# ForceSensingBase_Schematics.net
KiCad netlist of a schematic drawn in EasyEDA
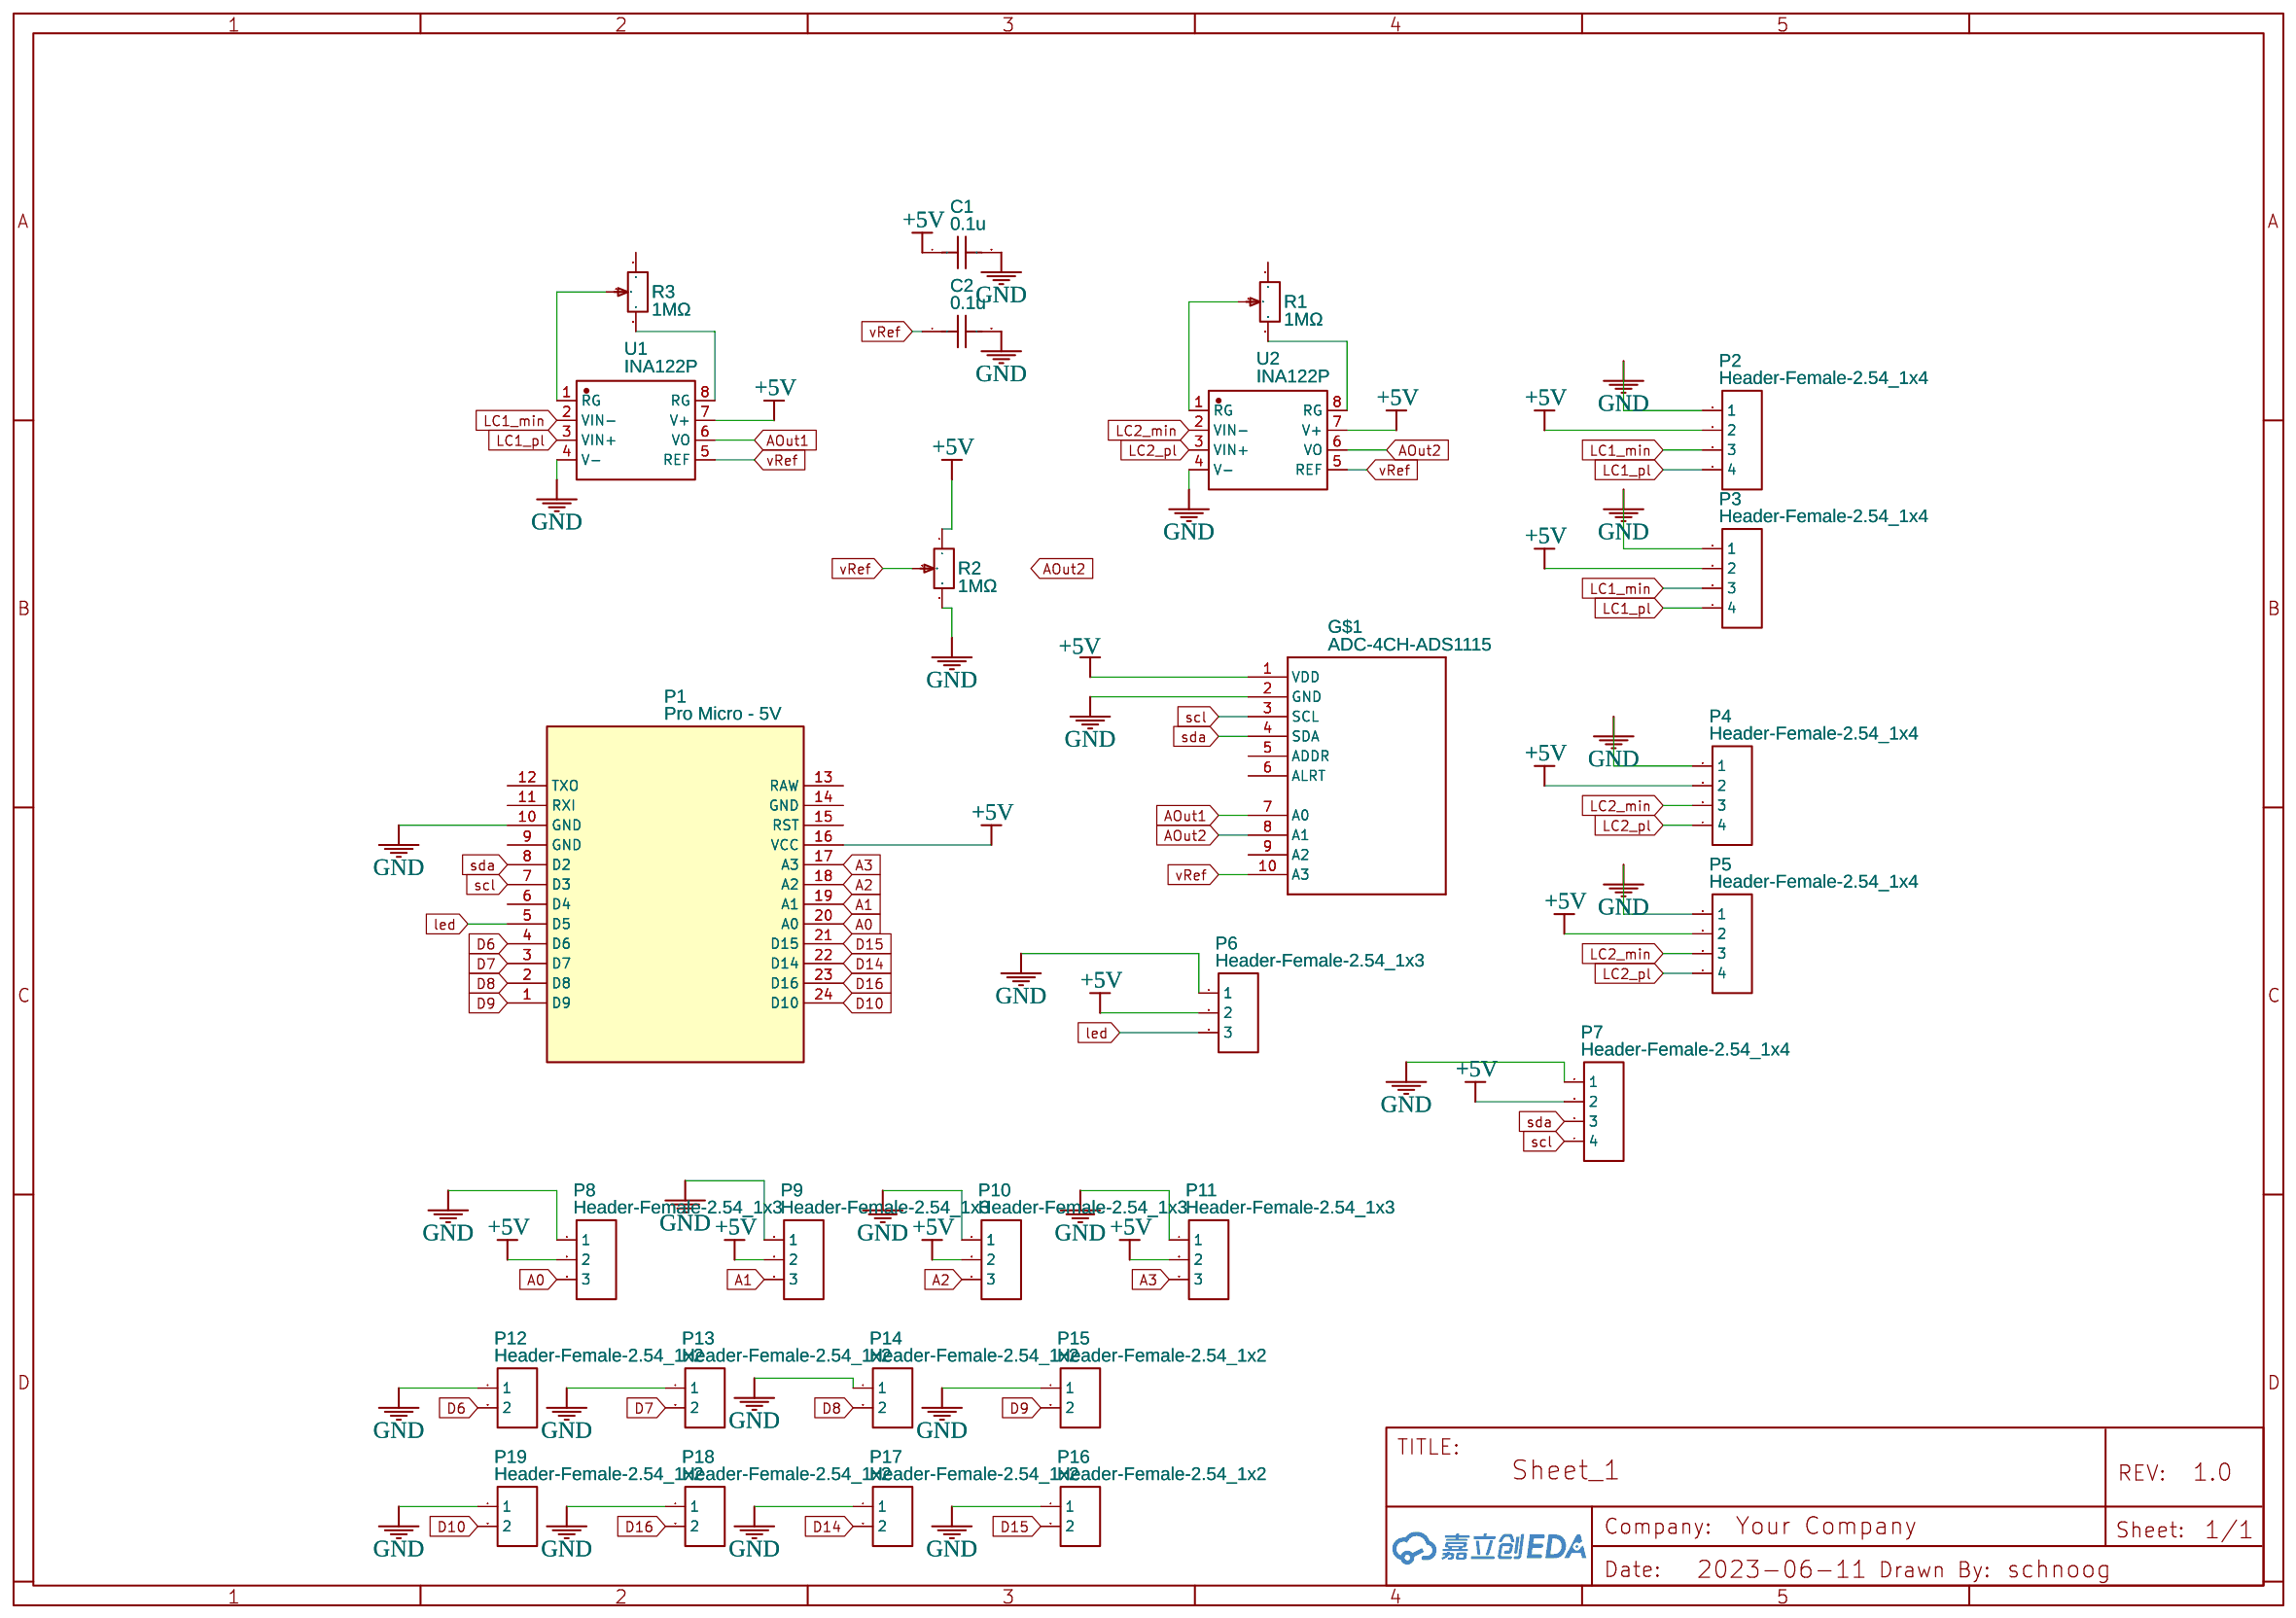
[diagram p0: schematic sheet]

(export (version "E")
  (design (tool "Eeschema 10.0.6"))
  (components
    (comp (ref "C1") (value "0.1u") (libsource (lib "") (part "C_1206_US")))
    (comp (ref "C2") (value "0.1u") (libsource (lib "") (part "C_1206_US")))
    (comp (ref "G$1") (value "ADC-4CH-ADS1115") (libsource (lib "") (part "ADC-4CH-ADS1115")))
    (comp (ref "P1") (value "Pro Micro - 5V") (libsource (lib "") (part "Pro Micro - 5V")))
    (comp (ref "P2")
      (value "Header-Female-2.54_1x4")
      (fields (field (name "BOM_Supplier Part") "C124413"))
      (libsource (lib "") (part "Header-Female-2.54_1x4"))
    )
    (comp (ref "P3")
      (value "Header-Female-2.54_1x4")
      (fields (field (name "BOM_Supplier Part") "C124413"))
      (libsource (lib "") (part "Header-Female-2.54_1x4"))
    )
    (comp (ref "P4")
      (value "Header-Female-2.54_1x4")
      (fields (field (name "BOM_Supplier Part") "C124413"))
      (libsource (lib "") (part "Header-Female-2.54_1x4"))
    )
    (comp (ref "P5")
      (value "Header-Female-2.54_1x4")
      (fields (field (name "BOM_Supplier Part") "C124413"))
      (libsource (lib "") (part "Header-Female-2.54_1x4"))
    )
    (comp (ref "P6")
      (value "Header-Female-2.54_1x3")
      (fields
        (field (name "BOM_Manufacturer Part") "2.54-1*3P母")
        (field (name "BOM_Supplier Part") "C146243")
      )
      (libsource (lib "") (part "Header-Female-2.54_1x3"))
    )
    (comp (ref "P7")
      (value "Header-Female-2.54_1x4")
      (fields (field (name "BOM_Supplier Part") "C124413"))
      (libsource (lib "") (part "Header-Female-2.54_1x4"))
    )
    (comp (ref "P8")
      (value "Header-Female-2.54_1x3")
      (fields
        (field (name "BOM_Manufacturer Part") "2.54-1*3P母")
        (field (name "BOM_Supplier Part") "C146243")
      )
      (libsource (lib "") (part "Header-Female-2.54_1x3"))
    )
    (comp (ref "P9")
      (value "Header-Female-2.54_1x3")
      (fields
        (field (name "BOM_Manufacturer Part") "2.54-1*3P母")
        (field (name "BOM_Supplier Part") "C146243")
      )
      (libsource (lib "") (part "Header-Female-2.54_1x3"))
    )
    (comp (ref "P10")
      (value "Header-Female-2.54_1x3")
      (fields
        (field (name "BOM_Manufacturer Part") "2.54-1*3P母")
        (field (name "BOM_Supplier Part") "C146243")
      )
      (libsource (lib "") (part "Header-Female-2.54_1x3"))
    )
    (comp (ref "P11")
      (value "Header-Female-2.54_1x3")
      (fields
        (field (name "BOM_Manufacturer Part") "2.54-1*3P母")
        (field (name "BOM_Supplier Part") "C146243")
      )
      (libsource (lib "") (part "Header-Female-2.54_1x3"))
    )
    (comp (ref "P12")
      (value "Header-Female-2.54_1x2")
      (fields (field (name "BOM_Manufacturer Part") "2.54-1*2P母") (field (name "BOM_Supplier Part") "C49661"))
      (libsource (lib "") (part "Header-Female-2.54_1x2"))
    )
    (comp (ref "P13")
      (value "Header-Female-2.54_1x2")
      (fields (field (name "BOM_Manufacturer Part") "2.54-1*2P母") (field (name "BOM_Supplier Part") "C49661"))
      (libsource (lib "") (part "Header-Female-2.54_1x2"))
    )
    (comp (ref "P14")
      (value "Header-Female-2.54_1x2")
      (fields (field (name "BOM_Manufacturer Part") "2.54-1*2P母") (field (name "BOM_Supplier Part") "C49661"))
      (libsource (lib "") (part "Header-Female-2.54_1x2"))
    )
    (comp (ref "P15")
      (value "Header-Female-2.54_1x2")
      (fields (field (name "BOM_Manufacturer Part") "2.54-1*2P母") (field (name "BOM_Supplier Part") "C49661"))
      (libsource (lib "") (part "Header-Female-2.54_1x2"))
    )
    (comp (ref "P16")
      (value "Header-Female-2.54_1x2")
      (fields (field (name "BOM_Manufacturer Part") "2.54-1*2P母") (field (name "BOM_Supplier Part") "C49661"))
      (libsource (lib "") (part "Header-Female-2.54_1x2"))
    )
    (comp (ref "P17")
      (value "Header-Female-2.54_1x2")
      (fields (field (name "BOM_Manufacturer Part") "2.54-1*2P母") (field (name "BOM_Supplier Part") "C49661"))
      (libsource (lib "") (part "Header-Female-2.54_1x2"))
    )
    (comp (ref "P18")
      (value "Header-Female-2.54_1x2")
      (fields (field (name "BOM_Manufacturer Part") "2.54-1*2P母") (field (name "BOM_Supplier Part") "C49661"))
      (libsource (lib "") (part "Header-Female-2.54_1x2"))
    )
    (comp (ref "P19")
      (value "Header-Female-2.54_1x2")
      (fields (field (name "BOM_Manufacturer Part") "2.54-1*2P母") (field (name "BOM_Supplier Part") "C49661"))
      (libsource (lib "") (part "Header-Female-2.54_1x2"))
    )
    (comp (ref "R1")
      (value "1MΩ")
      (fields
        (field (name "BOM_Manufacturer Part") "3296W-1-105LF")
        (field (name "BOM_Supplier Part") "C83687")
      )
      (libsource (lib "") (part "3296W-1-105LF"))
    )
    (comp (ref "R2")
      (value "1MΩ")
      (fields
        (field (name "BOM_Manufacturer Part") "3296W-1-105LF")
        (field (name "BOM_Supplier Part") "C83687")
      )
      (libsource (lib "") (part "3296W-1-105LF"))
    )
    (comp (ref "R3")
      (value "1MΩ")
      (fields
        (field (name "BOM_Manufacturer Part") "3296W-1-105LF")
        (field (name "BOM_Supplier Part") "C83687")
      )
      (libsource (lib "") (part "3296W-1-105LF"))
    )
    (comp (ref "U1")
      (value "INA122P")
      (fields (field (name "BOM_Supplier Part") "C1346816"))
      (libsource (lib "") (part "INA122P"))
    )
    (comp (ref "U2")
      (value "INA122P")
      (fields (field (name "BOM_Supplier Part") "C1346816"))
      (libsource (lib "") (part "INA122P"))
    )
  )
  (nets
    (net (code "1") (name "+5V") (class "Default")
      (node (ref "C1") (pin "1") (pinfunction "1_1") (pintype "unspecified"))
      (node (ref "G$1") (pin "1") (pinfunction "VDD_1") (pintype "bidirectional"))
      (node (ref "P1") (pin "16") (pinfunction "VCC_16") (pintype "unspecified"))
      (node (ref "P10") (pin "2") (pinfunction "2_2") (pintype "input"))
      (node (ref "P11") (pin "2") (pinfunction "2_2") (pintype "input"))
      (node (ref "P2") (pin "2") (pinfunction "2_2") (pintype "input"))
      (node (ref "P3") (pin "2") (pinfunction "2_2") (pintype "input"))
      (node (ref "P4") (pin "2") (pinfunction "2_2") (pintype "input"))
      (node (ref "P5") (pin "2") (pinfunction "2_2") (pintype "input"))
      (node (ref "P6") (pin "2") (pinfunction "2_2") (pintype "input"))
      (node (ref "P7") (pin "2") (pinfunction "2_2") (pintype "input"))
      (node (ref "P8") (pin "2") (pinfunction "2_2") (pintype "input"))
      (node (ref "P9") (pin "2") (pinfunction "2_2") (pintype "input"))
      (node (ref "R2") (pin "1") (pinfunction "1_1") (pintype "input"))
      (node (ref "U1") (pin "7") (pinfunction "V+_7") (pintype "unspecified"))
      (node (ref "U2") (pin "7") (pinfunction "V+_7") (pintype "unspecified"))
    )
    (net (code "2") (name "A0") (class "Default")
      (node (ref "P1") (pin "20") (pinfunction "A0_20") (pintype "unspecified"))
      (node (ref "P8") (pin "3") (pinfunction "3_3") (pintype "input"))
    )
    (net (code "3") (name "A1") (class "Default")
      (node (ref "P1") (pin "19") (pinfunction "A1_19") (pintype "unspecified"))
      (node (ref "P9") (pin "3") (pinfunction "3_3") (pintype "input"))
    )
    (net (code "4") (name "A2") (class "Default")
      (node (ref "P1") (pin "18") (pinfunction "A2_18") (pintype "unspecified"))
      (node (ref "P10") (pin "3") (pinfunction "3_3") (pintype "input"))
    )
    (net (code "5") (name "A3") (class "Default")
      (node (ref "P1") (pin "17") (pinfunction "A3_17") (pintype "unspecified"))
      (node (ref "P11") (pin "3") (pinfunction "3_3") (pintype "input"))
    )
    (net (code "6") (name "AOut1") (class "Default")
      (node (ref "G$1") (pin "7") (pinfunction "A0_7") (pintype "bidirectional"))
      (node (ref "U1") (pin "6") (pinfunction "VO_6") (pintype "unspecified"))
    )
    (net (code "7") (name "AOut2") (class "Default")
      (node (ref "G$1") (pin "8") (pinfunction "A1_8") (pintype "bidirectional"))
      (node (ref "U2") (pin "6") (pinfunction "VO_6") (pintype "unspecified"))
    )
    (net (code "8") (name "D6") (class "Default")
      (node (ref "P1") (pin "4") (pinfunction "D6_4") (pintype "unspecified"))
      (node (ref "P12") (pin "2") (pinfunction "2_2") (pintype "input"))
    )
    (net (code "9") (name "D7") (class "Default")
      (node (ref "P1") (pin "3") (pinfunction "D7_3") (pintype "unspecified"))
      (node (ref "P13") (pin "2") (pinfunction "2_2") (pintype "input"))
    )
    (net (code "10") (name "D8") (class "Default")
      (node (ref "P1") (pin "2") (pinfunction "D8_2") (pintype "unspecified"))
      (node (ref "P14") (pin "2") (pinfunction "2_2") (pintype "input"))
    )
    (net (code "11") (name "D9") (class "Default")
      (node (ref "P1") (pin "1") (pinfunction "D9_1") (pintype "unspecified"))
      (node (ref "P15") (pin "2") (pinfunction "2_2") (pintype "input"))
    )
    (net (code "12") (name "D10") (class "Default")
      (node (ref "P1") (pin "24") (pinfunction "D10_24") (pintype "unspecified"))
      (node (ref "P19") (pin "2") (pinfunction "2_2") (pintype "input"))
    )
    (net (code "13") (name "D14") (class "Default")
      (node (ref "P1") (pin "22") (pinfunction "D14_22") (pintype "unspecified"))
      (node (ref "P17") (pin "2") (pinfunction "2_2") (pintype "input"))
    )
    (net (code "14") (name "D15") (class "Default")
      (node (ref "P1") (pin "21") (pinfunction "D15_21") (pintype "unspecified"))
      (node (ref "P16") (pin "2") (pinfunction "2_2") (pintype "input"))
    )
    (net (code "15") (name "D16") (class "Default")
      (node (ref "P1") (pin "23") (pinfunction "D16_23") (pintype "unspecified"))
      (node (ref "P18") (pin "2") (pinfunction "2_2") (pintype "input"))
    )
    (net (code "16") (name "GND") (class "Default")
      (node (ref "C1") (pin "2") (pinfunction "2_2") (pintype "unspecified"))
      (node (ref "C2") (pin "2") (pinfunction "2_2") (pintype "unspecified"))
      (node (ref "G$1") (pin "2") (pinfunction "GND_2") (pintype "bidirectional"))
      (node (ref "P1") (pin "10") (pinfunction "GND_10") (pintype "unspecified"))
      (node (ref "P10") (pin "1") (pinfunction "1_1") (pintype "input"))
      (node (ref "P11") (pin "1") (pinfunction "1_1") (pintype "input"))
      (node (ref "P12") (pin "1") (pinfunction "1_1") (pintype "input"))
      (node (ref "P13") (pin "1") (pinfunction "1_1") (pintype "input"))
      (node (ref "P14") (pin "1") (pinfunction "1_1") (pintype "input"))
      (node (ref "P15") (pin "1") (pinfunction "1_1") (pintype "input"))
      (node (ref "P16") (pin "1") (pinfunction "1_1") (pintype "input"))
      (node (ref "P17") (pin "1") (pinfunction "1_1") (pintype "input"))
      (node (ref "P18") (pin "1") (pinfunction "1_1") (pintype "input"))
      (node (ref "P19") (pin "1") (pinfunction "1_1") (pintype "input"))
      (node (ref "P2") (pin "1") (pinfunction "1_1") (pintype "input"))
      (node (ref "P3") (pin "1") (pinfunction "1_1") (pintype "input"))
      (node (ref "P4") (pin "1") (pinfunction "1_1") (pintype "input"))
      (node (ref "P5") (pin "1") (pinfunction "1_1") (pintype "input"))
      (node (ref "P6") (pin "1") (pinfunction "1_1") (pintype "input"))
      (node (ref "P7") (pin "1") (pinfunction "1_1") (pintype "input"))
      (node (ref "P8") (pin "1") (pinfunction "1_1") (pintype "input"))
      (node (ref "P9") (pin "1") (pinfunction "1_1") (pintype "input"))
      (node (ref "R2") (pin "3") (pinfunction "3_3") (pintype "input"))
      (node (ref "U1") (pin "4") (pinfunction "V-_4") (pintype "unspecified"))
      (node (ref "U2") (pin "4") (pinfunction "V-_4") (pintype "unspecified"))
    )
    (net (code "17") (name "LC1_min") (class "Default")
      (node (ref "P2") (pin "3") (pinfunction "3_3") (pintype "input"))
      (node (ref "P3") (pin "3") (pinfunction "3_3") (pintype "input"))
      (node (ref "U1") (pin "2") (pinfunction "VIN-_2") (pintype "unspecified"))
    )
    (net (code "18") (name "LC1_pl") (class "Default")
      (node (ref "P2") (pin "4") (pinfunction "4_4") (pintype "input"))
      (node (ref "P3") (pin "4") (pinfunction "4_4") (pintype "input"))
      (node (ref "U1") (pin "3") (pinfunction "VIN+_3") (pintype "unspecified"))
    )
    (net (code "19") (name "LC2_min") (class "Default")
      (node (ref "P4") (pin "3") (pinfunction "3_3") (pintype "input"))
      (node (ref "P5") (pin "3") (pinfunction "3_3") (pintype "input"))
      (node (ref "U2") (pin "2") (pinfunction "VIN-_2") (pintype "unspecified"))
    )
    (net (code "20") (name "LC2_pl") (class "Default")
      (node (ref "P4") (pin "4") (pinfunction "4_4") (pintype "input"))
      (node (ref "P5") (pin "4") (pinfunction "4_4") (pintype "input"))
      (node (ref "U2") (pin "3") (pinfunction "VIN+_3") (pintype "unspecified"))
    )
    (net (code "21") (name "Net-(R1-Pad2)") (class "Default")
      (node (ref "R1") (pin "2") (pinfunction "2_2") (pintype "input"))
      (node (ref "U2") (pin "1") (pinfunction "RG_1") (pintype "unspecified"))
    )
    (net (code "22") (name "Net-(R1-Pad3)") (class "Default")
      (node (ref "R1") (pin "3") (pinfunction "3_3") (pintype "input"))
      (node (ref "U2") (pin "8") (pinfunction "RG_8") (pintype "unspecified"))
    )
    (net (code "23") (name "Net-(R3-Pad2)") (class "Default")
      (node (ref "R3") (pin "2") (pinfunction "2_2") (pintype "input"))
      (node (ref "U1") (pin "1") (pinfunction "RG_1") (pintype "unspecified"))
    )
    (net (code "24") (name "Net-(R3-Pad3)") (class "Default")
      (node (ref "R3") (pin "3") (pinfunction "3_3") (pintype "input"))
      (node (ref "U1") (pin "8") (pinfunction "RG_8") (pintype "unspecified"))
    )
    (net (code "25") (name "led") (class "Default")
      (node (ref "P1") (pin "5") (pinfunction "D5_5") (pintype "unspecified"))
      (node (ref "P6") (pin "3") (pinfunction "3_3") (pintype "input"))
    )
    (net (code "26") (name "scl") (class "Default")
      (node (ref "G$1") (pin "3") (pinfunction "SCL_3") (pintype "bidirectional"))
      (node (ref "P1") (pin "7") (pinfunction "D3_7") (pintype "unspecified"))
      (node (ref "P7") (pin "4") (pinfunction "4_4") (pintype "input"))
    )
    (net (code "27") (name "sda") (class "Default")
      (node (ref "G$1") (pin "4") (pinfunction "SDA_4") (pintype "bidirectional"))
      (node (ref "P1") (pin "8") (pinfunction "D2_8") (pintype "unspecified"))
      (node (ref "P7") (pin "3") (pinfunction "3_3") (pintype "input"))
    )
    (net (code "28") (name "unconnected-(G$1-A2-Pad9)") (class "Default")
      (node (ref "G$1") (pin "9") (pinfunction "A2_9") (pintype "bidirectional"))
    )
    (net (code "29") (name "unconnected-(G$1-ADDR-Pad5)") (class "Default")
      (node (ref "G$1") (pin "5") (pinfunction "ADDR_5") (pintype "bidirectional"))
    )
    (net (code "30") (name "unconnected-(G$1-ALRT-Pad6)") (class "Default")
      (node (ref "G$1") (pin "6") (pinfunction "ALRT_6") (pintype "bidirectional"))
    )
    (net (code "31") (name "unconnected-(P1-D4-Pad6)") (class "Default")
      (node (ref "P1") (pin "6") (pinfunction "D4_6") (pintype "unspecified"))
    )
    (net (code "32") (name "unconnected-(P1-GND-Pad9)") (class "Default")
      (node (ref "P1") (pin "9") (pinfunction "GND_9") (pintype "unspecified"))
    )
    (net (code "33") (name "unconnected-(P1-GND-Pad14)") (class "Default")
      (node (ref "P1") (pin "14") (pinfunction "GND_14") (pintype "unspecified"))
    )
    (net (code "34") (name "unconnected-(P1-RAW-Pad13)") (class "Default")
      (node (ref "P1") (pin "13") (pinfunction "RAW_13") (pintype "unspecified"))
    )
    (net (code "35") (name "unconnected-(P1-RST-Pad15)") (class "Default")
      (node (ref "P1") (pin "15") (pinfunction "RST_15") (pintype "unspecified"))
    )
    (net (code "36") (name "unconnected-(P1-RXI-Pad11)") (class "Default")
      (node (ref "P1") (pin "11") (pinfunction "RXI_11") (pintype "unspecified"))
    )
    (net (code "37") (name "unconnected-(P1-TXO-Pad12)") (class "Default")
      (node (ref "P1") (pin "12") (pinfunction "TXO_12") (pintype "unspecified"))
    )
    (net (code "38") (name "unconnected-(R1-Pad1)") (class "Default")
      (node (ref "R1") (pin "1") (pinfunction "1_1") (pintype "input"))
    )
    (net (code "39") (name "unconnected-(R3-Pad1)") (class "Default")
      (node (ref "R3") (pin "1") (pinfunction "1_1") (pintype "input"))
    )
    (net (code "40") (name "vRef") (class "Default")
      (node (ref "C2") (pin "1") (pinfunction "1_1") (pintype "unspecified"))
      (node (ref "G$1") (pin "10") (pinfunction "A3_10") (pintype "bidirectional"))
      (node (ref "R2") (pin "2") (pinfunction "2_2") (pintype "input"))
      (node (ref "U1") (pin "5") (pinfunction "REF_5") (pintype "unspecified"))
      (node (ref "U2") (pin "5") (pinfunction "REF_5") (pintype "unspecified"))
    )
  )
)
